# ProPrj___2024-11-02.net
KiCad netlist of a schematic drawn in EasyEDA Pro
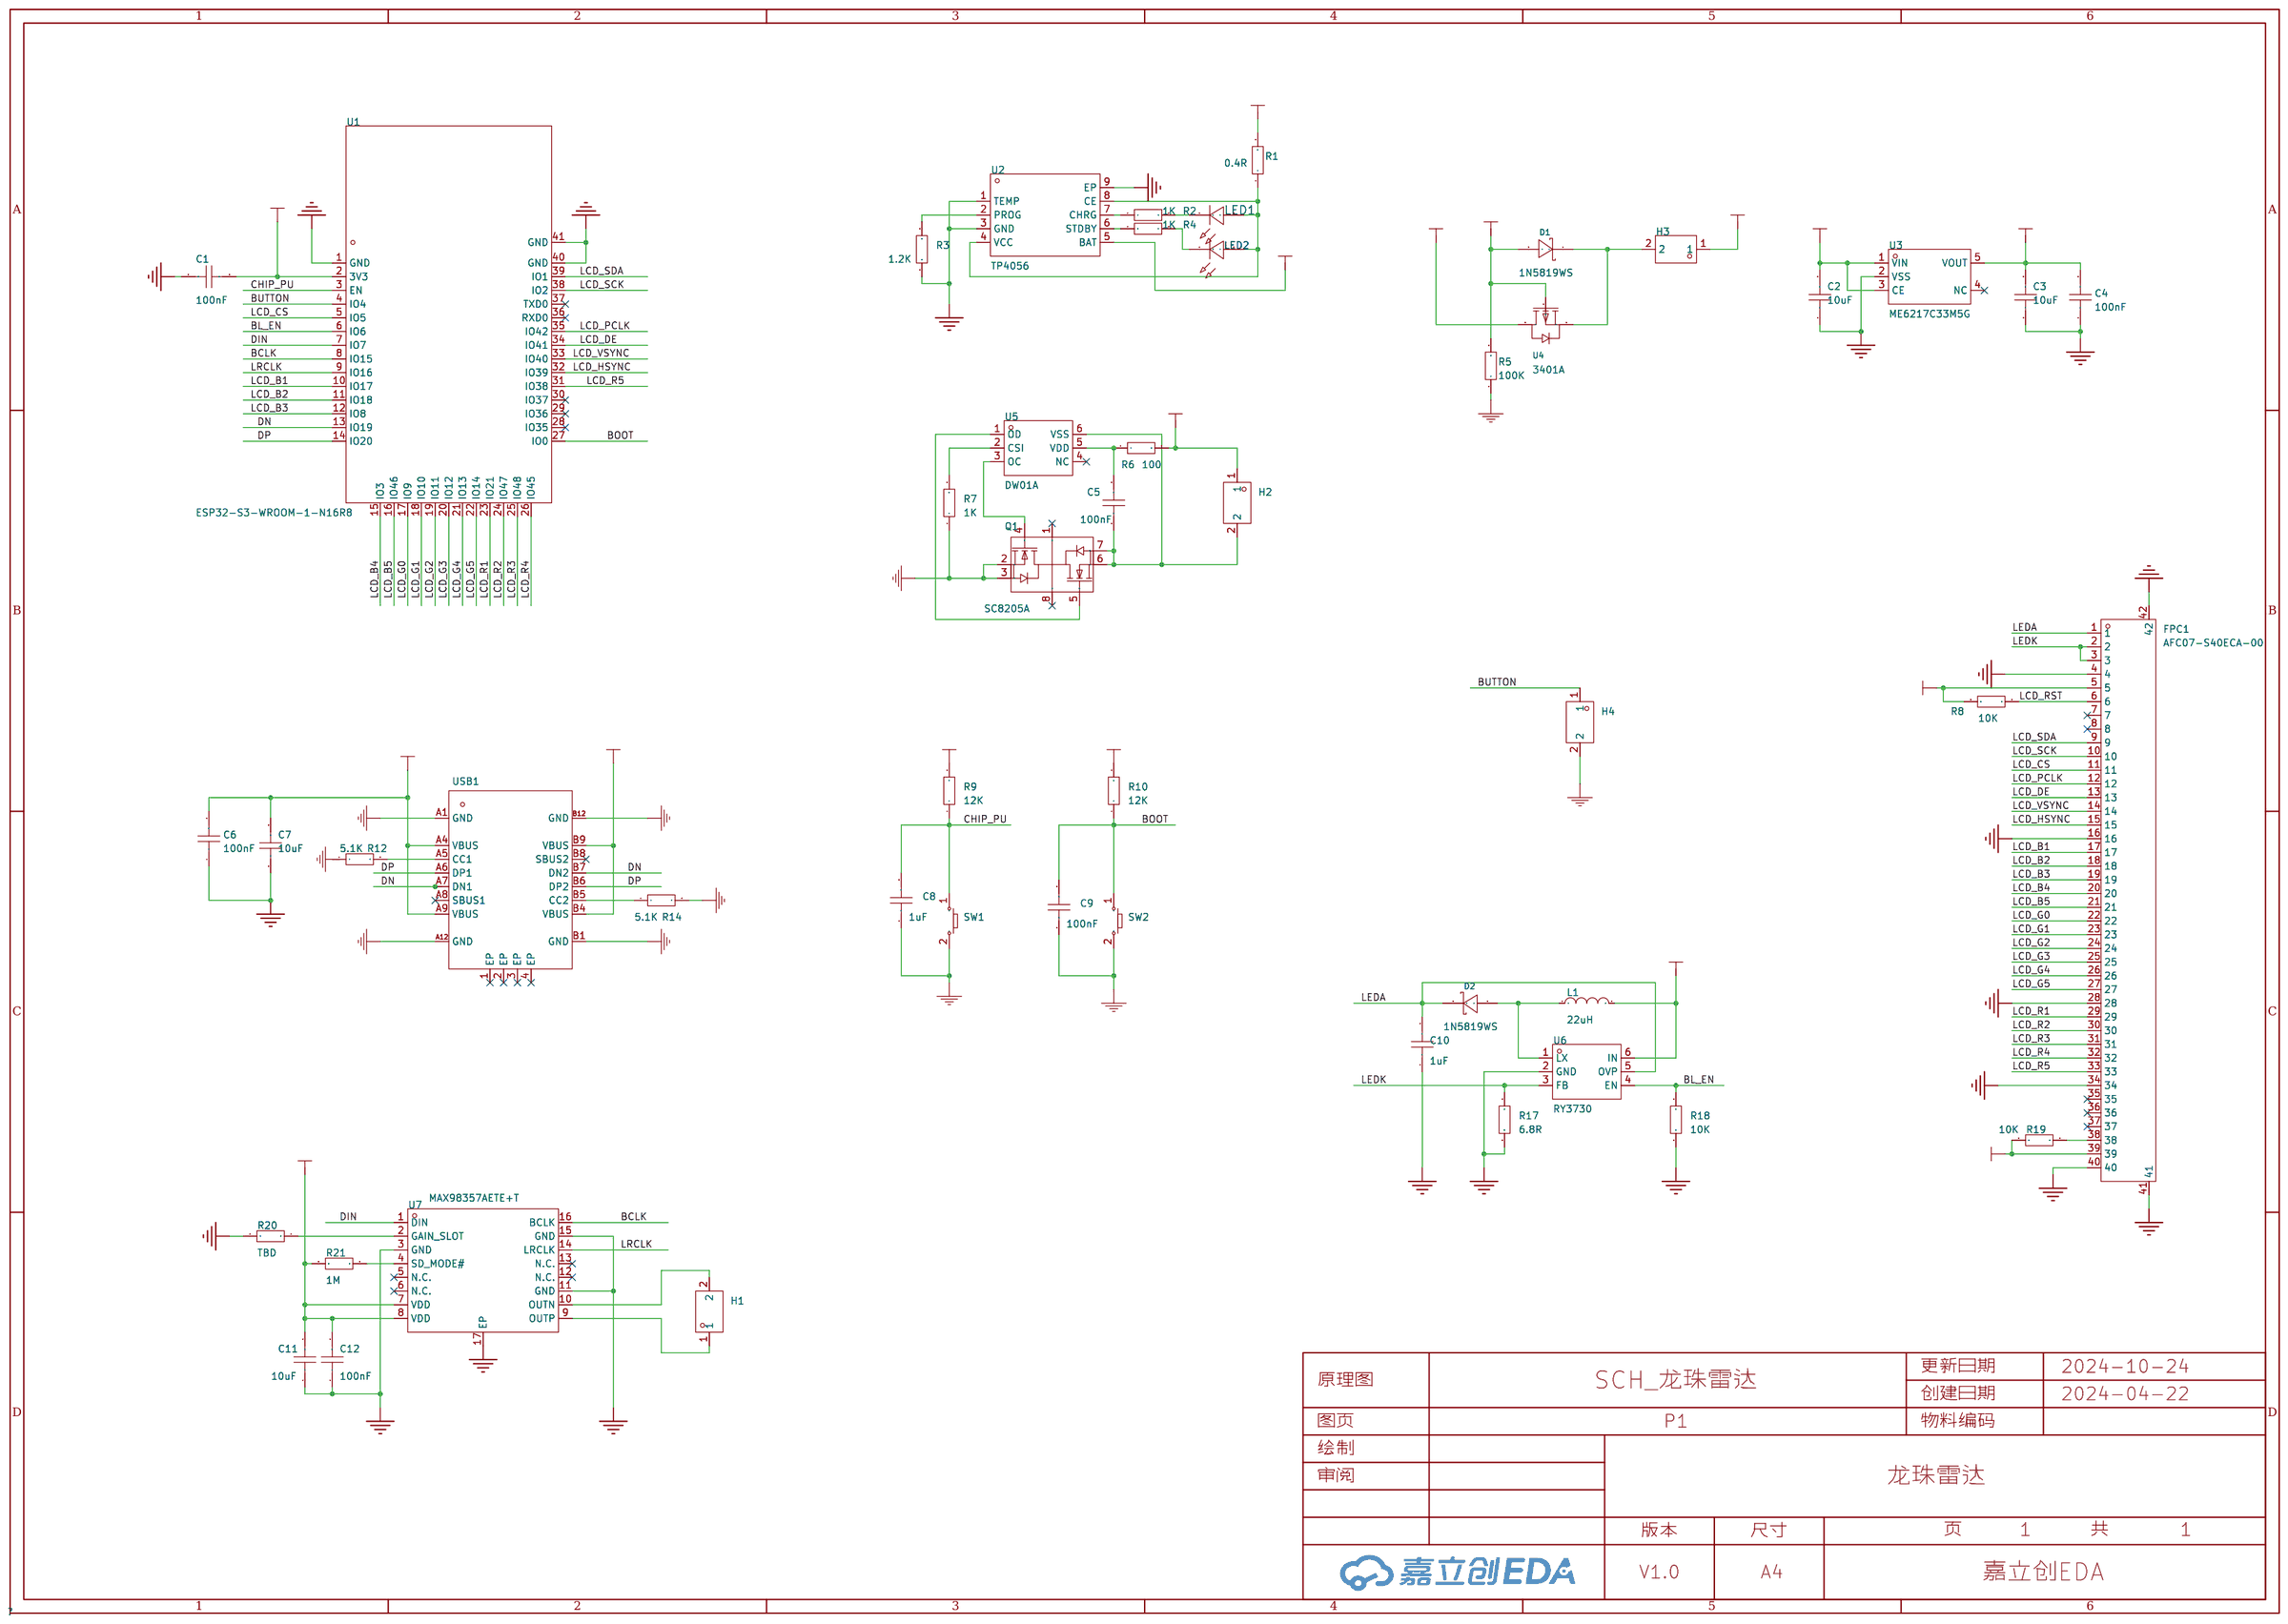
[diagram p0: schematic sheet]

(export (version "E")
  (design (tool "Eeschema 10.0.6"))
  (components
    (comp (ref "C1")
      (value "100nF")
      (footprint "easyedapro:C0603")
      (libsource (lib "easyedapro") (part "CapAcitance"))
    )
    (comp (ref "C2")
      (value "10uF")
      (footprint "easyedapro:C0603")
      (libsource (lib "easyedapro") (part "CapAcitance"))
    )
    (comp (ref "C3")
      (value "10uF")
      (footprint "easyedapro:C0603")
      (libsource (lib "easyedapro") (part "CapAcitance"))
    )
    (comp (ref "C4")
      (value "100nF")
      (footprint "easyedapro:C0603")
      (libsource (lib "easyedapro") (part "CapAcitance"))
    )
    (comp (ref "C5")
      (value "100nF")
      (footprint "easyedapro:C0603")
      (libsource (lib "easyedapro") (part "CapAcitance"))
    )
    (comp (ref "C6")
      (value "100nF")
      (footprint "easyedapro:C0603")
      (libsource (lib "easyedapro") (part "CapAcitance"))
    )
    (comp (ref "C7")
      (value "10uF")
      (footprint "easyedapro:C0603")
      (libsource (lib "easyedapro") (part "CapAcitance"))
    )
    (comp (ref "C8")
      (value "1uF")
      (footprint "easyedapro:C0603")
      (libsource (lib "easyedapro") (part "CapAcitance"))
    )
    (comp (ref "C9")
      (value "100nF")
      (footprint "easyedapro:C0603")
      (libsource (lib "easyedapro") (part "CapAcitance"))
    )
    (comp (ref "C10")
      (value "1uF")
      (footprint "easyedapro:C0603")
      (libsource (lib "easyedapro") (part "CapAcitance"))
    )
    (comp (ref "C11")
      (value "10uF")
      (footprint "easyedapro:C0603")
      (libsource (lib "easyedapro") (part "CapAcitance"))
    )
    (comp (ref "C12")
      (value "100nF")
      (footprint "easyedapro:C0603")
      (libsource (lib "easyedapro") (part "CapAcitance"))
    )
    (comp (ref "D1")
      (value "1N5819WS")
      (footprint "easyedapro:SOD-323_L1.8-W1.3-LS2.5-RD")
      (description "直流反向耐压(Vr):40V;平均整流电流(Io):1A;正向压降(Vf):600mV@1A;")
      (fields (field (name "Manufacturer") "Hottech(合科泰)"))
      (libsource (lib "easyedapro") (part "1N5819WS"))
    )
    (comp (ref "D2")
      (value "1N5819WS")
      (footprint "easyedapro:SOD-323_L1.8-W1.3-LS2.5-RD")
      (description "直流反向耐压(Vr):40V;平均整流电流(Io):1A;正向压降(Vf):600mV@1A;")
      (fields (field (name "Manufacturer") "Hottech(合科泰)"))
      (libsource (lib "easyedapro") (part "1N5819WS"))
    )
    (comp (ref "FPC1")
      (value "AFC07-S40ECA-00")
      (footprint "easyedapro:FPC-SMD_P0.50-40P_LCS-SJ-H2.0")
      (description "锁定特性:抽屉式;触点类型:上接;触点数量:40P;间距:0.5mm;安装类型:卧贴;")
      (fields (field (name "Manufacturer") "JS(钜硕电子)"))
      (libsource (lib "easyedapro") (part "AFC07-S40ECA-00"))
    )
    (comp (ref "H1")
      (value "~")
      (footprint "easyedapro:HDR-TH_2P-P2.54-V-M-2")
      (libsource (lib "easyedapro") (part "HDR-M-2.54_2x1"))
    )
    (comp (ref "H2")
      (value "~")
      (footprint "easyedapro:HDR-TH_2P-P2.54-V-M-2")
      (libsource (lib "easyedapro") (part "HDR-M-2.54_2x1"))
    )
    (comp (ref "H3")
      (value "~")
      (footprint "easyedapro:HDR-TH_2P-P2.54-V-M-2")
      (libsource (lib "easyedapro") (part "HDR-M-2.54_2x1"))
    )
    (comp (ref "H4")
      (value "~")
      (footprint "easyedapro:HDR-TH_2P-P2.54-V-M-2")
      (libsource (lib "easyedapro") (part "HDR-M-2.54_2x1"))
    )
    (comp (ref "L1")
      (value "22uH")
      (footprint "easyedapro:IND-SMD_L4.5-W4.0_CD43")
      (description "电感值:22uH;精度:±20%;额定电流:760mA;类型:-;")
      (fields (field (name "Manufacturer Part") "CD43-220M 22UH") (field (name "Manufacturer") "DMBJ(振宝佳)"))
      (libsource (lib "easyedapro") (part "CD43-220M"))
    )
    (comp (ref "LED1")
      (value "~")
      (footprint "easyedapro:LED_0603")
      (libsource (lib "easyedapro") (part "LED_R"))
    )
    (comp (ref "LED2")
      (value "~")
      (footprint "easyedapro:LED_0603")
      (libsource (lib "easyedapro") (part "LED_G"))
    )
    (comp (ref "Q1")
      (value "SC8205A")
      (footprint "easyedapro:TSSOP-8_L4.4-W3.0-P0.65-LS6.4-BL")
      (fields (field (name "Manufacturer") "FM(富满)"))
      (libsource (lib "easyedapro") (part "SC8205A"))
    )
    (comp (ref "R1") (value "0.4R") (footprint "easyedapro:R0402") (libsource (lib "easyedapro") (part "电阻")))
    (comp (ref "R2") (value "1K") (footprint "easyedapro:R0402") (libsource (lib "easyedapro") (part "电阻")))
    (comp (ref "R3") (value "1.2K") (footprint "easyedapro:R0402") (libsource (lib "easyedapro") (part "电阻")))
    (comp (ref "R4") (value "1K") (footprint "easyedapro:R0402") (libsource (lib "easyedapro") (part "电阻")))
    (comp (ref "R5") (value "100K") (footprint "easyedapro:R0402") (libsource (lib "easyedapro") (part "电阻")))
    (comp (ref "R6") (value "100") (footprint "easyedapro:R0402") (libsource (lib "easyedapro") (part "电阻")))
    (comp (ref "R7") (value "1K") (footprint "easyedapro:R0402") (libsource (lib "easyedapro") (part "电阻")))
    (comp (ref "R8") (value "10K") (footprint "easyedapro:R0402") (libsource (lib "easyedapro") (part "电阻")))
    (comp (ref "R9") (value "12K") (footprint "easyedapro:R0402") (libsource (lib "easyedapro") (part "电阻")))
    (comp (ref "R10") (value "12K") (footprint "easyedapro:R0402") (libsource (lib "easyedapro") (part "电阻")))
    (comp (ref "R12")
      (value "5.1K")
      (footprint "easyedapro:R0402")
      (libsource (lib "easyedapro") (part "电阻"))
    )
    (comp (ref "R14")
      (value "5.1K")
      (footprint "easyedapro:R0402")
      (libsource (lib "easyedapro") (part "电阻"))
    )
    (comp (ref "R17")
      (value "6.8R")
      (footprint "easyedapro:R0402")
      (libsource (lib "easyedapro") (part "电阻"))
    )
    (comp (ref "R18") (value "10K") (footprint "easyedapro:R0402") (libsource (lib "easyedapro") (part "电阻")))
    (comp (ref "R19") (value "10K") (footprint "easyedapro:R0402") (libsource (lib "easyedapro") (part "电阻")))
    (comp (ref "R20") (value "TBD") (footprint "easyedapro:R0402") (libsource (lib "easyedapro") (part "电阻")))
    (comp (ref "R21") (value "1M") (footprint "easyedapro:R0402") (libsource (lib "easyedapro") (part "电阻")))
    (comp (ref "SW1")
      (value "~")
      (footprint "easyedapro:Key_SMD_3x4x2")
      (libsource (lib "easyedapro") (part "轻触按键x2"))
    )
    (comp (ref "SW2")
      (value "~")
      (footprint "easyedapro:Key_SMD_3x4x2")
      (libsource (lib "easyedapro") (part "轻触按键x2"))
    )
    (comp (ref "U1")
      (value "ESP32-S3-WROOM-1-N16R8")
      (footprint "easyedapro:WIRELM-SMD_ESP32-S3-WROOM-1")
      (fields (field (name "Manufacturer") "ESPRESSIF(乐鑫)"))
      (libsource (lib "easyedapro") (part "ESP32-S3-WROOM-1(N16R8)"))
    )
    (comp (ref "U2")
      (value "TP4056")
      (footprint "easyedapro:ESOP-8_L4.9-W3.9-P1.27-LS6.0-BL-EP")
      (libsource (lib "easyedapro") (part "TP4056_C9900002169"))
    )
    (comp (ref "U3")
      (value "ME6217C33M5G")
      (footprint "easyedapro:SOT-23-5_L3.0-W1.7-P0.95-LS2.8-BR")
      (description "输出类型:固定;最大输入电压:7V;输出电压:3.3V;最大输出电流:800mA;电源纹波抑制比(PSRR):65dB@(1kHz);输出极性:正极;")
      (fields (field (name "Manufacturer") "MICRONE(南京微盟)"))
      (libsource (lib "easyedapro") (part "ME6217C33M5G"))
    )
    (comp (ref "U4")
      (value "3401A")
      (footprint "easyedapro:SOT-23-3_L2.9-W1.3-P1.90-LS2.4-BR")
      (description "类型:P沟道;漏源电压(Vdss):30V;连续漏极电流(Id):4.5A;导通电阻(RDS(on)@Vgs,Id):42mΩ;阈值电压(Vgs(th)@Id):1.3V;")
      (fields (field (name "Manufacturer") "HL(富海微)"))
      (libsource (lib "easyedapro") (part "3401A"))
    )
    (comp (ref "U5")
      (value "DW01A")
      (footprint "easyedapro:SOT-23-6_L2.9-W1.6-P0.95-LS2.8-BL")
      (description "电源电压:-300mV~8V;最大充电电流:-;电池类型:锂离子/聚合物;电池节数:1;")
      (fields (field (name "Manufacturer") "YONGYUTAI(永裕泰)"))
      (libsource (lib "easyedapro") (part "DW01A_C2927799"))
    )
    (comp (ref "U6")
      (value "RY3730")
      (footprint "easyedapro:SOT-23-6_L2.9-W1.6-P0.95-LS2.8-BL")
      (fields (field (name "Manufacturer") "RYCHiP(蕊源)"))
      (libsource (lib "easyedapro") (part "RY3730"))
    )
    (comp (ref "U7")
      (value "MAX98357AETE+T")
      (footprint "easyedapro:TQFN-16_L3.0-W3.0-P0.50-BL-EP1.5")
      (description "功放类型:-;扬声器通道数:单声道;输出功率:3.2Wx2@4Ω;")
      (fields (field (name "Manufacturer") "ADI(亚德诺)/MAXIM(美信)"))
      (libsource (lib "easyedapro") (part "MAX98357AETE+T"))
    )
    (comp (ref "USB1")
      (value "~")
      (footprint "easyedapro:USB_TYPE-C-16P")
      (libsource (lib "easyedapro") (part "USB_TYPE-C-16P"))
    )
  )
  (nets
    (net (code "1") (name "/BCLK") (class "Default")
      (node (ref "U1") (pin "8") (pinfunction "IO15_8") (pintype "unspecified"))
      (node (ref "U7") (pin "16") (pinfunction "BCLK_16") (pintype "unspecified"))
    )
    (net (code "2") (name "/BL_EN") (class "Default")
      (node (ref "R18") (pin "1") (pinfunction "1_1") (pintype "input"))
      (node (ref "U1") (pin "6") (pinfunction "IO6_6") (pintype "unspecified"))
      (node (ref "U6") (pin "4") (pinfunction "EN_4") (pintype "input"))
    )
    (net (code "3") (name "/BOOT") (class "Default")
      (node (ref "C9") (pin "2") (pinfunction "2_2") (pintype "input"))
      (node (ref "R10") (pin "1") (pinfunction "1_1") (pintype "input"))
      (node (ref "SW2") (pin "1") (pinfunction "1_1") (pintype "input"))
      (node (ref "U1") (pin "27") (pinfunction "IO0_27") (pintype "unspecified"))
    )
    (net (code "4") (name "/BUTTON") (class "Default")
      (node (ref "H4") (pin "1") (pinfunction "1_1") (pintype "input"))
      (node (ref "U1") (pin "4") (pinfunction "IO4_4") (pintype "unspecified"))
    )
    (net (code "5") (name "/CHIP_PU") (class "Default")
      (node (ref "C8") (pin "2") (pinfunction "2_2") (pintype "input"))
      (node (ref "R9") (pin "1") (pinfunction "1_1") (pintype "input"))
      (node (ref "SW1") (pin "1") (pinfunction "1_1") (pintype "input"))
      (node (ref "U1") (pin "3") (pinfunction "EN_3") (pintype "unspecified"))
    )
    (net (code "6") (name "/DIN") (class "Default")
      (node (ref "U1") (pin "7") (pinfunction "IO7_7") (pintype "unspecified"))
      (node (ref "U7") (pin "1") (pinfunction "DIN_1") (pintype "unspecified"))
    )
    (net (code "7") (name "/DN") (class "Default")
      (node (ref "U1") (pin "13") (pinfunction "IO19_13") (pintype "unspecified"))
      (node (ref "USB1") (pin "A7") (pinfunction "DN1_A7") (pintype "input"))
      (node (ref "USB1") (pin "B7") (pinfunction "DN2_B7") (pintype "input"))
    )
    (net (code "8") (name "/DP") (class "Default")
      (node (ref "U1") (pin "14") (pinfunction "IO20_14") (pintype "unspecified"))
      (node (ref "USB1") (pin "A6") (pinfunction "DP1_A6") (pintype "input"))
      (node (ref "USB1") (pin "B6") (pinfunction "DP2_B6") (pintype "input"))
    )
    (net (code "9") (name "/LCD_B1") (class "Default")
      (node (ref "FPC1") (pin "17") (pinfunction "17_17") (pintype "unspecified"))
      (node (ref "U1") (pin "10") (pinfunction "IO17_10") (pintype "unspecified"))
    )
    (net (code "10") (name "/LCD_B2") (class "Default")
      (node (ref "FPC1") (pin "18") (pinfunction "18_18") (pintype "unspecified"))
      (node (ref "U1") (pin "11") (pinfunction "IO18_11") (pintype "unspecified"))
    )
    (net (code "11") (name "/LCD_B3") (class "Default")
      (node (ref "FPC1") (pin "19") (pinfunction "19_19") (pintype "unspecified"))
      (node (ref "U1") (pin "12") (pinfunction "IO8_12") (pintype "unspecified"))
    )
    (net (code "12") (name "/LCD_B4") (class "Default")
      (node (ref "FPC1") (pin "20") (pinfunction "20_20") (pintype "unspecified"))
      (node (ref "U1") (pin "15") (pinfunction "IO3_15") (pintype "unspecified"))
    )
    (net (code "13") (name "/LCD_B5") (class "Default")
      (node (ref "FPC1") (pin "21") (pinfunction "21_21") (pintype "unspecified"))
      (node (ref "U1") (pin "16") (pinfunction "IO46_16") (pintype "unspecified"))
    )
    (net (code "14") (name "/LCD_CS") (class "Default")
      (node (ref "FPC1") (pin "11") (pinfunction "11_11") (pintype "unspecified"))
      (node (ref "U1") (pin "5") (pinfunction "IO5_5") (pintype "unspecified"))
    )
    (net (code "15") (name "/LCD_DE") (class "Default")
      (node (ref "FPC1") (pin "13") (pinfunction "13_13") (pintype "unspecified"))
      (node (ref "U1") (pin "34") (pinfunction "IO41_34") (pintype "unspecified"))
    )
    (net (code "16") (name "/LCD_G0") (class "Default")
      (node (ref "FPC1") (pin "22") (pinfunction "22_22") (pintype "unspecified"))
      (node (ref "U1") (pin "17") (pinfunction "IO9_17") (pintype "unspecified"))
    )
    (net (code "17") (name "/LCD_G1") (class "Default")
      (node (ref "FPC1") (pin "23") (pinfunction "23_23") (pintype "unspecified"))
      (node (ref "U1") (pin "18") (pinfunction "IO10_18") (pintype "unspecified"))
    )
    (net (code "18") (name "/LCD_G2") (class "Default")
      (node (ref "FPC1") (pin "24") (pinfunction "24_24") (pintype "unspecified"))
      (node (ref "U1") (pin "19") (pinfunction "IO11_19") (pintype "unspecified"))
    )
    (net (code "19") (name "/LCD_G3") (class "Default")
      (node (ref "FPC1") (pin "25") (pinfunction "25_25") (pintype "unspecified"))
      (node (ref "U1") (pin "20") (pinfunction "IO12_20") (pintype "unspecified"))
    )
    (net (code "20") (name "/LCD_G4") (class "Default")
      (node (ref "FPC1") (pin "26") (pinfunction "26_26") (pintype "unspecified"))
      (node (ref "U1") (pin "21") (pinfunction "IO13_21") (pintype "unspecified"))
    )
    (net (code "21") (name "/LCD_G5") (class "Default")
      (node (ref "FPC1") (pin "27") (pinfunction "27_27") (pintype "unspecified"))
      (node (ref "U1") (pin "22") (pinfunction "IO14_22") (pintype "unspecified"))
    )
    (net (code "22") (name "/LCD_HSYNC") (class "Default")
      (node (ref "FPC1") (pin "15") (pinfunction "15_15") (pintype "unspecified"))
      (node (ref "U1") (pin "32") (pinfunction "IO39_32") (pintype "unspecified"))
    )
    (net (code "23") (name "/LCD_PCLK") (class "Default")
      (node (ref "FPC1") (pin "12") (pinfunction "12_12") (pintype "unspecified"))
      (node (ref "U1") (pin "35") (pinfunction "IO42_35") (pintype "unspecified"))
    )
    (net (code "24") (name "/LCD_R1") (class "Default")
      (node (ref "FPC1") (pin "29") (pinfunction "29_29") (pintype "unspecified"))
      (node (ref "U1") (pin "23") (pinfunction "IO21_23") (pintype "unspecified"))
    )
    (net (code "25") (name "/LCD_R2") (class "Default")
      (node (ref "FPC1") (pin "30") (pinfunction "30_30") (pintype "unspecified"))
      (node (ref "U1") (pin "24") (pinfunction "IO47_24") (pintype "unspecified"))
    )
    (net (code "26") (name "/LCD_R3") (class "Default")
      (node (ref "FPC1") (pin "31") (pinfunction "31_31") (pintype "unspecified"))
      (node (ref "U1") (pin "25") (pinfunction "IO48_25") (pintype "unspecified"))
    )
    (net (code "27") (name "/LCD_R4") (class "Default")
      (node (ref "FPC1") (pin "32") (pinfunction "32_32") (pintype "unspecified"))
      (node (ref "U1") (pin "26") (pinfunction "IO45_26") (pintype "unspecified"))
    )
    (net (code "28") (name "/LCD_R5") (class "Default")
      (node (ref "FPC1") (pin "33") (pinfunction "33_33") (pintype "unspecified"))
      (node (ref "U1") (pin "31") (pinfunction "IO38_31") (pintype "unspecified"))
    )
    (net (code "29") (name "/LCD_RST") (class "Default")
      (node (ref "FPC1") (pin "6") (pinfunction "6_6") (pintype "unspecified"))
      (node (ref "R8") (pin "1") (pinfunction "1_1") (pintype "input"))
    )
    (net (code "30") (name "/LCD_SCK") (class "Default")
      (node (ref "FPC1") (pin "10") (pinfunction "10_10") (pintype "unspecified"))
      (node (ref "U1") (pin "38") (pinfunction "IO2_38") (pintype "unspecified"))
    )
    (net (code "31") (name "/LCD_SDA") (class "Default")
      (node (ref "FPC1") (pin "9") (pinfunction "9_9") (pintype "unspecified"))
      (node (ref "U1") (pin "39") (pinfunction "IO1_39") (pintype "unspecified"))
    )
    (net (code "32") (name "/LCD_VSYNC") (class "Default")
      (node (ref "FPC1") (pin "14") (pinfunction "14_14") (pintype "unspecified"))
      (node (ref "U1") (pin "33") (pinfunction "IO40_33") (pintype "unspecified"))
    )
    (net (code "33") (name "/LEDA") (class "Default")
      (node (ref "C10") (pin "2") (pinfunction "2_2") (pintype "input"))
      (node (ref "D2") (pin "1") (pinfunction "K_1") (pintype "input"))
      (node (ref "FPC1") (pin "1") (pinfunction "1_1") (pintype "unspecified"))
      (node (ref "U6") (pin "5") (pinfunction "OVP_5") (pintype "input"))
    )
    (net (code "34") (name "/LEDK") (class "Default")
      (node (ref "FPC1") (pin "2") (pinfunction "2_2") (pintype "unspecified"))
      (node (ref "FPC1") (pin "3") (pinfunction "3_3") (pintype "unspecified"))
      (node (ref "R17") (pin "1") (pinfunction "1_1") (pintype "input"))
      (node (ref "U6") (pin "3") (pinfunction "FB_3") (pintype "input"))
    )
    (net (code "35") (name "/LRCLK") (class "Default")
      (node (ref "U1") (pin "9") (pinfunction "IO16_9") (pintype "unspecified"))
      (node (ref "U7") (pin "14") (pinfunction "LRCLK_14") (pintype "unspecified"))
    )
    (net (code "36") (name "3V3") (class "Default")
      (node (ref "C1") (pin "1") (pinfunction "1_1") (pintype "input"))
      (node (ref "C3") (pin "2") (pinfunction "2_2") (pintype "input"))
      (node (ref "C4") (pin "2") (pinfunction "2_2") (pintype "input"))
      (node (ref "FPC1") (pin "39") (pinfunction "39_39") (pintype "unspecified"))
      (node (ref "FPC1") (pin "5") (pinfunction "5_5") (pintype "unspecified"))
      (node (ref "R10") (pin "2") (pinfunction "2_2") (pintype "input"))
      (node (ref "R19") (pin "2") (pinfunction "2_2") (pintype "input"))
      (node (ref "R8") (pin "2") (pinfunction "2_2") (pintype "input"))
      (node (ref "R9") (pin "2") (pinfunction "2_2") (pintype "input"))
      (node (ref "U1") (pin "2") (pinfunction "3V3_2") (pintype "unspecified"))
      (node (ref "U3") (pin "5") (pinfunction "VOUT_5") (pintype "unspecified"))
    )
    (net (code "37") (name "BAT+") (class "Default")
      (node (ref "H2") (pin "1") (pinfunction "1_1") (pintype "input"))
      (node (ref "R6") (pin "2") (pinfunction "2_2") (pintype "input"))
      (node (ref "U2") (pin "5") (pinfunction "BAT_5") (pintype "unspecified"))
      (node (ref "U4") (pin "3") (pinfunction "D_3") (pintype "input"))
    )
    (net (code "38") (name "GND") (class "Default")
      (node (ref "C1") (pin "2") (pinfunction "2_2") (pintype "input"))
      (node (ref "C10") (pin "1") (pinfunction "1_1") (pintype "input"))
      (node (ref "C11") (pin "1") (pinfunction "1_1") (pintype "input"))
      (node (ref "C12") (pin "1") (pinfunction "1_1") (pintype "input"))
      (node (ref "C2") (pin "1") (pinfunction "1_1") (pintype "input"))
      (node (ref "C3") (pin "1") (pinfunction "1_1") (pintype "input"))
      (node (ref "C4") (pin "1") (pinfunction "1_1") (pintype "input"))
      (node (ref "C6") (pin "1") (pinfunction "1_1") (pintype "input"))
      (node (ref "C7") (pin "1") (pinfunction "1_1") (pintype "input"))
      (node (ref "C8") (pin "1") (pinfunction "1_1") (pintype "input"))
      (node (ref "C9") (pin "1") (pinfunction "1_1") (pintype "input"))
      (node (ref "FPC1") (pin "16") (pinfunction "16_16") (pintype "unspecified"))
      (node (ref "FPC1") (pin "28") (pinfunction "28_28") (pintype "unspecified"))
      (node (ref "FPC1") (pin "34") (pinfunction "34_34") (pintype "unspecified"))
      (node (ref "FPC1") (pin "4") (pinfunction "4_4") (pintype "unspecified"))
      (node (ref "FPC1") (pin "40") (pinfunction "40_40") (pintype "unspecified"))
      (node (ref "FPC1") (pin "41") (pinfunction "41_41") (pintype "unspecified"))
      (node (ref "FPC1") (pin "42") (pinfunction "42_42") (pintype "unspecified"))
      (node (ref "H4") (pin "2") (pinfunction "2_2") (pintype "input"))
      (node (ref "Q1") (pin "2") (pinfunction "S1_2") (pintype "input"))
      (node (ref "Q1") (pin "3") (pinfunction "S1_3") (pintype "input"))
      (node (ref "R12") (pin "1") (pinfunction "1_1") (pintype "input"))
      (node (ref "R14") (pin "2") (pinfunction "2_2") (pintype "input"))
      (node (ref "R17") (pin "2") (pinfunction "2_2") (pintype "input"))
      (node (ref "R18") (pin "2") (pinfunction "2_2") (pintype "input"))
      (node (ref "R20") (pin "2") (pinfunction "2_2") (pintype "input"))
      (node (ref "R3") (pin "1") (pinfunction "1_1") (pintype "input"))
      (node (ref "R5") (pin "1") (pinfunction "1_1") (pintype "input"))
      (node (ref "R7") (pin "1") (pinfunction "1_1") (pintype "input"))
      (node (ref "SW1") (pin "2") (pinfunction "2_2") (pintype "input"))
      (node (ref "SW2") (pin "2") (pinfunction "2_2") (pintype "input"))
      (node (ref "U1") (pin "1") (pinfunction "GND_1") (pintype "unspecified"))
      (node (ref "U1") (pin "40") (pinfunction "GND_40") (pintype "unspecified"))
      (node (ref "U1") (pin "41") (pinfunction "GND_41") (pintype "unspecified"))
      (node (ref "U2") (pin "1") (pinfunction "TEMP_1") (pintype "unspecified"))
      (node (ref "U2") (pin "3") (pinfunction "GND_3") (pintype "unspecified"))
      (node (ref "U2") (pin "9") (pinfunction "EP_9") (pintype "unspecified"))
      (node (ref "U3") (pin "2") (pinfunction "VSS_2") (pintype "unspecified"))
      (node (ref "U6") (pin "2") (pinfunction "GND_2") (pintype "input"))
      (node (ref "U7") (pin "11") (pinfunction "GND_11") (pintype "unspecified"))
      (node (ref "U7") (pin "15") (pinfunction "GND_15") (pintype "unspecified"))
      (node (ref "U7") (pin "17") (pinfunction "EP_17") (pintype "unspecified"))
      (node (ref "U7") (pin "3") (pinfunction "GND_3") (pintype "unspecified"))
      (node (ref "USB1") (pin "A1") (pinfunction "GND_A1") (pintype "input"))
      (node (ref "USB1") (pin "A12") (pinfunction "GND_A12") (pintype "input"))
      (node (ref "USB1") (pin "B1") (pinfunction "GND_B1") (pintype "input"))
      (node (ref "USB1") (pin "B12") (pinfunction "GND_B12") (pintype "input"))
    )
    (net (code "39") (name "Net-(D1-K)") (class "Default")
      (node (ref "D1") (pin "1") (pinfunction "K_1") (pintype "input"))
      (node (ref "H3") (pin "2") (pinfunction "2_2") (pintype "input"))
      (node (ref "U4") (pin "2") (pinfunction "S_2") (pintype "input"))
    )
    (net (code "40") (name "Net-(D2-A)") (class "Default")
      (node (ref "D2") (pin "2") (pinfunction "A_2") (pintype "input"))
      (node (ref "L1") (pin "1") (pinfunction "1_1") (pintype "unspecified"))
      (node (ref "U6") (pin "1") (pinfunction "LX_1") (pintype "input"))
    )
    (net (code "41") (name "Net-(FPC1-Pad38)") (class "Default")
      (node (ref "FPC1") (pin "38") (pinfunction "38_38") (pintype "unspecified"))
      (node (ref "R19") (pin "1") (pinfunction "1_1") (pintype "input"))
    )
    (net (code "42") (name "Net-(LED1-A)") (class "Default")
      (node (ref "LED1") (pin "2") (pinfunction "A_2") (pintype "input"))
      (node (ref "LED2") (pin "2") (pinfunction "A_2") (pintype "input"))
      (node (ref "R1") (pin "1") (pinfunction "1_1") (pintype "input"))
      (node (ref "U2") (pin "4") (pinfunction "VCC_4") (pintype "unspecified"))
      (node (ref "U2") (pin "8") (pinfunction "CE_8") (pintype "unspecified"))
    )
    (net (code "43") (name "Net-(LED1-C)") (class "Default")
      (node (ref "LED1") (pin "1") (pinfunction "C_1") (pintype "input"))
      (node (ref "R2") (pin "2") (pinfunction "2_2") (pintype "input"))
    )
    (net (code "44") (name "Net-(LED2-C)") (class "Default")
      (node (ref "LED2") (pin "1") (pinfunction "C_1") (pintype "input"))
      (node (ref "R4") (pin "2") (pinfunction "2_2") (pintype "input"))
    )
    (net (code "45") (name "Net-(Q1-G1)") (class "Default")
      (node (ref "Q1") (pin "4") (pinfunction "G1_4") (pintype "input"))
      (node (ref "U5") (pin "3") (pinfunction "OC_3") (pintype "unspecified"))
    )
    (net (code "46") (name "Net-(Q1-G2)") (class "Default")
      (node (ref "Q1") (pin "5") (pinfunction "G2_5") (pintype "input"))
      (node (ref "U5") (pin "1") (pinfunction "OD_1") (pintype "unspecified"))
    )
    (net (code "47") (name "Net-(U2-CHRG)") (class "Default")
      (node (ref "R2") (pin "1") (pinfunction "1_1") (pintype "input"))
      (node (ref "U2") (pin "7") (pinfunction "CHRG_7") (pintype "unspecified"))
    )
    (net (code "48") (name "Net-(U2-PROG)") (class "Default")
      (node (ref "R3") (pin "2") (pinfunction "2_2") (pintype "input"))
      (node (ref "U2") (pin "2") (pinfunction "PROG_2") (pintype "unspecified"))
    )
    (net (code "49") (name "Net-(U2-STDBY)") (class "Default")
      (node (ref "R4") (pin "1") (pinfunction "1_1") (pintype "input"))
      (node (ref "U2") (pin "6") (pinfunction "STDBY_6") (pintype "unspecified"))
    )
    (net (code "50") (name "Net-(U5-CSI)") (class "Default")
      (node (ref "R7") (pin "2") (pinfunction "2_2") (pintype "input"))
      (node (ref "U5") (pin "2") (pinfunction "CSI_2") (pintype "unspecified"))
    )
    (net (code "51") (name "Net-(U5-VDD)") (class "Default")
      (node (ref "C5") (pin "2") (pinfunction "2_2") (pintype "input"))
      (node (ref "R6") (pin "1") (pinfunction "1_1") (pintype "input"))
      (node (ref "U5") (pin "5") (pinfunction "VDD_5") (pintype "unspecified"))
    )
    (net (code "52") (name "Net-(U5-VSS)") (class "Default")
      (node (ref "C5") (pin "1") (pinfunction "1_1") (pintype "input"))
      (node (ref "H2") (pin "2") (pinfunction "2_2") (pintype "input"))
      (node (ref "Q1") (pin "6") (pinfunction "S2_6") (pintype "input"))
      (node (ref "Q1") (pin "7") (pinfunction "S2_7") (pintype "input"))
      (node (ref "U5") (pin "6") (pinfunction "VSS_6") (pintype "unspecified"))
    )
    (net (code "53") (name "Net-(U7-GAIN_SLOT)") (class "Default")
      (node (ref "R20") (pin "1") (pinfunction "1_1") (pintype "input"))
      (node (ref "U7") (pin "2") (pinfunction "GAIN_SLOT_2") (pintype "unspecified"))
    )
    (net (code "54") (name "Net-(U7-OUTN)") (class "Default")
      (node (ref "H1") (pin "2") (pinfunction "2_2") (pintype "input"))
      (node (ref "U7") (pin "10") (pinfunction "OUTN_10") (pintype "unspecified"))
    )
    (net (code "55") (name "Net-(U7-OUTP)") (class "Default")
      (node (ref "H1") (pin "1") (pinfunction "1_1") (pintype "input"))
      (node (ref "U7") (pin "9") (pinfunction "OUTP_9") (pintype "unspecified"))
    )
    (net (code "56") (name "Net-(U7-SD_MODE#)") (class "Default")
      (node (ref "R21") (pin "1") (pinfunction "1_1") (pintype "input"))
      (node (ref "U7") (pin "4") (pinfunction "SD_MODE#_4") (pintype "unspecified"))
    )
    (net (code "57") (name "Net-(USB1-CC1)") (class "Default")
      (node (ref "R12") (pin "2") (pinfunction "2_2") (pintype "input"))
      (node (ref "USB1") (pin "A5") (pinfunction "CC1_A5") (pintype "input"))
    )
    (net (code "58") (name "Net-(USB1-CC2)") (class "Default")
      (node (ref "R14") (pin "1") (pinfunction "1_1") (pintype "input"))
      (node (ref "USB1") (pin "B5") (pinfunction "CC2_B5") (pintype "input"))
    )
    (net (code "59") (name "VSYS") (class "Default")
      (node (ref "C11") (pin "2") (pinfunction "2_2") (pintype "input"))
      (node (ref "C12") (pin "2") (pinfunction "2_2") (pintype "input"))
      (node (ref "C2") (pin "2") (pinfunction "2_2") (pintype "input"))
      (node (ref "H3") (pin "1") (pinfunction "1_1") (pintype "input"))
      (node (ref "L1") (pin "2") (pinfunction "2_2") (pintype "unspecified"))
      (node (ref "R21") (pin "2") (pinfunction "2_2") (pintype "input"))
      (node (ref "U3") (pin "1") (pinfunction "VIN_1") (pintype "unspecified"))
      (node (ref "U3") (pin "3") (pinfunction "CE_3") (pintype "unspecified"))
      (node (ref "U6") (pin "6") (pinfunction "IN_6") (pintype "input"))
      (node (ref "U7") (pin "7") (pinfunction "VDD_7") (pintype "unspecified"))
      (node (ref "U7") (pin "8") (pinfunction "VDD_8") (pintype "unspecified"))
    )
    (net (code "60") (name "VUSB") (class "Default")
      (node (ref "C6") (pin "2") (pinfunction "2_2") (pintype "input"))
      (node (ref "C7") (pin "2") (pinfunction "2_2") (pintype "input"))
      (node (ref "D1") (pin "2") (pinfunction "A_2") (pintype "input"))
      (node (ref "R1") (pin "2") (pinfunction "2_2") (pintype "input"))
      (node (ref "R5") (pin "2") (pinfunction "2_2") (pintype "input"))
      (node (ref "U4") (pin "1") (pinfunction "G_1") (pintype "input"))
      (node (ref "USB1") (pin "A4") (pinfunction "VBUS_A4") (pintype "input"))
      (node (ref "USB1") (pin "A9") (pinfunction "VBUS_A9") (pintype "input"))
      (node (ref "USB1") (pin "B4") (pinfunction "VBUS_B4") (pintype "input"))
      (node (ref "USB1") (pin "B9") (pinfunction "VBUS_B9") (pintype "input"))
    )
    (net (code "61") (name "unconnected-(FPC1-Pad7)") (class "Default")
      (node (ref "FPC1") (pin "7") (pinfunction "7_7") (pintype "unspecified+no_connect"))
    )
    (net (code "62") (name "unconnected-(FPC1-Pad8)") (class "Default")
      (node (ref "FPC1") (pin "8") (pinfunction "8_8") (pintype "unspecified+no_connect"))
    )
    (net (code "63") (name "unconnected-(FPC1-Pad35)") (class "Default")
      (node (ref "FPC1") (pin "35") (pinfunction "35_35") (pintype "unspecified+no_connect"))
    )
    (net (code "64") (name "unconnected-(FPC1-Pad36)") (class "Default")
      (node (ref "FPC1") (pin "36") (pinfunction "36_36") (pintype "unspecified+no_connect"))
    )
    (net (code "65") (name "unconnected-(FPC1-Pad37)") (class "Default")
      (node (ref "FPC1") (pin "37") (pinfunction "37_37") (pintype "unspecified+no_connect"))
    )
    (net (code "66") (name "unconnected-(Q1-D12-Pad1)") (class "Default")
      (node (ref "Q1") (pin "1") (pinfunction "D12_1") (pintype "input+no_connect"))
    )
    (net (code "67") (name "unconnected-(Q1-D12-Pad8)") (class "Default")
      (node (ref "Q1") (pin "8") (pinfunction "D12_8") (pintype "input+no_connect"))
    )
    (net (code "68") (name "unconnected-(U1-IO35-Pad28)") (class "Default")
      (node (ref "U1") (pin "28") (pinfunction "IO35_28") (pintype "unspecified+no_connect"))
    )
    (net (code "69") (name "unconnected-(U1-IO36-Pad29)") (class "Default")
      (node (ref "U1") (pin "29") (pinfunction "IO36_29") (pintype "unspecified+no_connect"))
    )
    (net (code "70") (name "unconnected-(U1-IO37-Pad30)") (class "Default")
      (node (ref "U1") (pin "30") (pinfunction "IO37_30") (pintype "unspecified+no_connect"))
    )
    (net (code "71") (name "unconnected-(U1-RXD0-Pad36)") (class "Default")
      (node (ref "U1") (pin "36") (pinfunction "RXD0_36") (pintype "unspecified+no_connect"))
    )
    (net (code "72") (name "unconnected-(U1-TXD0-Pad37)") (class "Default")
      (node (ref "U1") (pin "37") (pinfunction "TXD0_37") (pintype "unspecified+no_connect"))
    )
    (net (code "73") (name "unconnected-(U3-NC-Pad4)") (class "Default")
      (node (ref "U3") (pin "4") (pinfunction "NC_4") (pintype "unspecified+no_connect"))
    )
    (net (code "74") (name "unconnected-(U5-NC-Pad4)") (class "Default")
      (node (ref "U5") (pin "4") (pinfunction "NC_4") (pintype "unspecified+no_connect"))
    )
    (net (code "75") (name "unconnected-(U7-N.C.-Pad5)") (class "Default")
      (node (ref "U7") (pin "5") (pinfunction "N.C._5") (pintype "unspecified+no_connect"))
    )
    (net (code "76") (name "unconnected-(U7-N.C.-Pad6)") (class "Default")
      (node (ref "U7") (pin "6") (pinfunction "N.C._6") (pintype "unspecified+no_connect"))
    )
    (net (code "77") (name "unconnected-(U7-N.C.-Pad12)") (class "Default")
      (node (ref "U7") (pin "12") (pinfunction "N.C._12") (pintype "unspecified+no_connect"))
    )
    (net (code "78") (name "unconnected-(U7-N.C.-Pad13)") (class "Default")
      (node (ref "U7") (pin "13") (pinfunction "N.C._13") (pintype "unspecified+no_connect"))
    )
    (net (code "79") (name "unconnected-(USB1-EP-Pad1)") (class "Default")
      (node (ref "USB1") (pin "1") (pinfunction "EP_1") (pintype "input+no_connect"))
    )
    (net (code "80") (name "unconnected-(USB1-EP-Pad2)") (class "Default")
      (node (ref "USB1") (pin "2") (pinfunction "EP_2") (pintype "input+no_connect"))
    )
    (net (code "81") (name "unconnected-(USB1-EP-Pad3)") (class "Default")
      (node (ref "USB1") (pin "3") (pinfunction "EP_3") (pintype "input+no_connect"))
    )
    (net (code "82") (name "unconnected-(USB1-EP-Pad4)") (class "Default")
      (node (ref "USB1") (pin "4") (pinfunction "EP_4") (pintype "input+no_connect"))
    )
    (net (code "83") (name "unconnected-(USB1-SBUS1-PadA8)") (class "Default")
      (node (ref "USB1") (pin "A8") (pinfunction "SBUS1_A8") (pintype "input+no_connect"))
    )
    (net (code "84") (name "unconnected-(USB1-SBUS2-PadB8)") (class "Default")
      (node (ref "USB1") (pin "B8") (pinfunction "SBUS2_B8") (pintype "input+no_connect"))
    )
  )
)
